# i2c.net
KiCad netlist of a schematic drawn in EAGLE
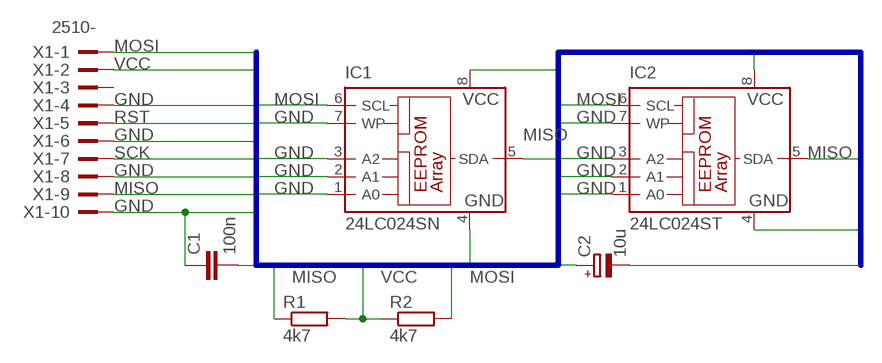
[diagram p0: schematic, sheet 1]

(export (version "E")
  (design (tool "Eeschema 10.0.6"))
  (components
    (comp (ref "C1")
      (value "100n")
      (footprint "eagle-import:C0805K")
      (libsource (lib "eagle-import") (part "C-EUC0805K"))
    )
    (comp (ref "C2")
      (value "10u")
      (footprint "eagle-import:SMC_D")
      (libsource (lib "eagle-import") (part "CPOL-EUSMCD"))
    )
    (comp (ref "IC1")
      (value "24LC024SN")
      (footprint "eagle-import:SO-08")
      (fields (field (name "MF") "MICROCHIP") (field (name "MPN") "24LC024/SN"))
      (libsource (lib "eagle-import") (part "24SNLC024"))
    )
    (comp (ref "IC2")
      (value "24LC024ST")
      (footprint "eagle-import:TSSOP8")
      (fields (field (name "MPN") "24LC024H-I/ST"))
      (libsource (lib "eagle-import") (part "24STLC024"))
    )
    (comp (ref "R1")
      (value "4k7")
      (footprint "eagle-import:0204_7")
      (libsource (lib "eagle-import") (part "R0204/7"))
    )
    (comp (ref "R2")
      (value "4k7")
      (footprint "eagle-import:0204_7")
      (libsource (lib "eagle-import") (part "R0204/7"))
    )
    (comp (ref "X1")
      (value "2510-")
      (footprint "eagle-import:PAK100_2500-10")
      (fields (field (name "MF") "3M") (field (name "MPN") "2510-6002UB"))
      (libsource (lib "eagle-import") (part "2510-"))
    )
  )
  (nets
    (net (code "1") (name "/GND") (class "Default")
      (node (ref "C1") (pin "1") (pinfunction "1_1") (pintype "passive"))
      (node (ref "C2") (pin "-") (pinfunction "-_-") (pintype "passive"))
      (node (ref "IC1") (pin "1") (pinfunction "A0_1") (pintype "input"))
      (node (ref "IC1") (pin "2") (pinfunction "A1_2") (pintype "input"))
      (node (ref "IC1") (pin "3") (pinfunction "A2_3") (pintype "input"))
      (node (ref "IC1") (pin "4") (pinfunction "GND_4") (pintype "power_in"))
      (node (ref "IC1") (pin "7") (pinfunction "WP_7") (pintype "input"))
      (node (ref "IC2") (pin "1") (pinfunction "A0_1") (pintype "input"))
      (node (ref "IC2") (pin "2") (pinfunction "A1_2") (pintype "input"))
      (node (ref "IC2") (pin "3") (pinfunction "A2_3") (pintype "input"))
      (node (ref "IC2") (pin "4") (pinfunction "GND_4") (pintype "power_in"))
      (node (ref "IC2") (pin "7") (pinfunction "WP_7") (pintype "input"))
      (node (ref "X1") (pin "10") (pinfunction "KL_10") (pintype "passive"))
      (node (ref "X1") (pin "4") (pinfunction "KL_4") (pintype "passive"))
      (node (ref "X1") (pin "6") (pinfunction "KL_6") (pintype "passive"))
      (node (ref "X1") (pin "8") (pinfunction "KL_8") (pintype "passive"))
    )
    (net (code "2") (name "/MISO") (class "Default")
      (node (ref "IC1") (pin "5") (pinfunction "SDA_5") (pintype "bidirectional"))
      (node (ref "IC2") (pin "5") (pinfunction "SDA_5") (pintype "bidirectional"))
      (node (ref "R1") (pin "1") (pinfunction "1_1") (pintype "passive"))
      (node (ref "X1") (pin "9") (pinfunction "KL_9") (pintype "passive"))
    )
    (net (code "3") (name "/MOSI") (class "Default")
      (node (ref "IC1") (pin "6") (pinfunction "SCL_6") (pintype "input"))
      (node (ref "IC2") (pin "6") (pinfunction "SCL_6") (pintype "input"))
      (node (ref "R2") (pin "2") (pinfunction "2_2") (pintype "passive"))
      (node (ref "X1") (pin "1") (pinfunction "KL_1") (pintype "passive"))
    )
    (net (code "4") (name "/RST") (class "Default")
      (node (ref "X1") (pin "5") (pinfunction "KL_5") (pintype "passive"))
    )
    (net (code "5") (name "/SCK") (class "Default")
      (node (ref "X1") (pin "7") (pinfunction "KL_7") (pintype "passive"))
    )
    (net (code "6") (name "/VCC") (class "Default")
      (node (ref "C1") (pin "2") (pinfunction "2_2") (pintype "passive"))
      (node (ref "C2") (pin "+") (pinfunction "+_+") (pintype "passive"))
      (node (ref "IC1") (pin "8") (pinfunction "VCC_8") (pintype "power_in"))
      (node (ref "IC2") (pin "8") (pinfunction "VCC_8") (pintype "power_in"))
      (node (ref "R1") (pin "2") (pinfunction "2_2") (pintype "passive"))
      (node (ref "R2") (pin "1") (pinfunction "1_1") (pintype "passive"))
      (node (ref "X1") (pin "2") (pinfunction "KL_2") (pintype "passive"))
    )
    (net (code "7") (name "unconnected-(X1D-KL-Pad3)") (class "Default")
      (node (ref "X1") (pin "3") (pinfunction "KL_3") (pintype "passive"))
    )
  )
)
